# Hallstop.net
KiCad netlist of a schematic drawn in EAGLE
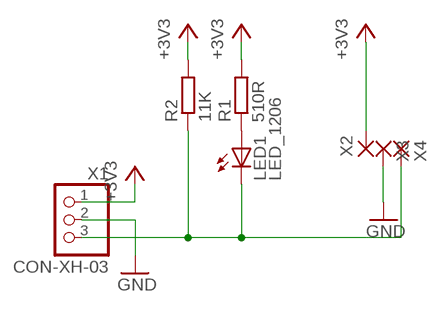
[diagram p0: schematic, sheet 1]

(export (version "E")
  (design (tool "Eeschema 10.0.6"))
  (components
    (comp (ref "LED1")
      (value "LED_1206")
      (footprint "eagle-import:LED1206")
      (libsource (lib "eagle-import") (part "LED_1206"))
    )
    (comp (ref "R1")
      (value "510R")
      (footprint "eagle-import:R0805")
      (libsource (lib "eagle-import") (part "R_0805"))
    )
    (comp (ref "R2")
      (value "11K")
      (footprint "eagle-import:R0805")
      (libsource (lib "eagle-import") (part "R_0805"))
    )
    (comp (ref "X1")
      (value "CON-XH-03")
      (footprint "eagle-import:XH-03")
      (libsource (lib "eagle-import") (part "CON-XH-03"))
    )
    (comp (ref "X2")
      (value "WIREPAD-SMD2")
      (footprint "eagle-import:PAD-1.27X2.54")
      (libsource (lib "eagle-import") (part "WIREPAD-SMD2"))
    )
    (comp (ref "X3")
      (value "WIREPAD-SMD2")
      (footprint "eagle-import:PAD-1.27X2.54")
      (libsource (lib "eagle-import") (part "WIREPAD-SMD2"))
    )
    (comp (ref "X4")
      (value "WIREPAD-SMD2")
      (footprint "eagle-import:PAD-1.27X2.54")
      (libsource (lib "eagle-import") (part "WIREPAD-SMD2"))
    )
  )
  (nets
    (net (code "1") (name "+3V3") (class "Default")
      (node (ref "R1") (pin "2") (pinfunction "2_2") (pintype "passive"))
      (node (ref "R2") (pin "2") (pinfunction "2_2") (pintype "passive"))
      (node (ref "X1") (pin "1") (pinfunction "1_1") (pintype "passive"))
      (node (ref "X2") (pin "P$1") (pinfunction "P_P$1") (pintype "passive"))
    )
    (net (code "2") (name "GND") (class "Default")
      (node (ref "X1") (pin "2") (pinfunction "2_2") (pintype "passive"))
      (node (ref "X3") (pin "P$1") (pinfunction "P_P$1") (pintype "passive"))
    )
    (net (code "3") (name "Net-(LED1-PadA)") (class "Default")
      (node (ref "LED1") (pin "A") (pinfunction "A_A") (pintype "passive"))
      (node (ref "R1") (pin "1") (pinfunction "1_1") (pintype "passive"))
    )
    (net (code "4") (name "Net-(X4-P)") (class "Default")
      (node (ref "LED1") (pin "C") (pinfunction "C_C") (pintype "passive"))
      (node (ref "R2") (pin "1") (pinfunction "1_1") (pintype "passive"))
      (node (ref "X1") (pin "3") (pinfunction "3_3") (pintype "passive"))
      (node (ref "X4") (pin "P$1") (pinfunction "P_P$1") (pintype "passive"))
    )
  )
)
